# Connections_Ports.net
KiCad netlist of a schematic drawn in Altium Designer
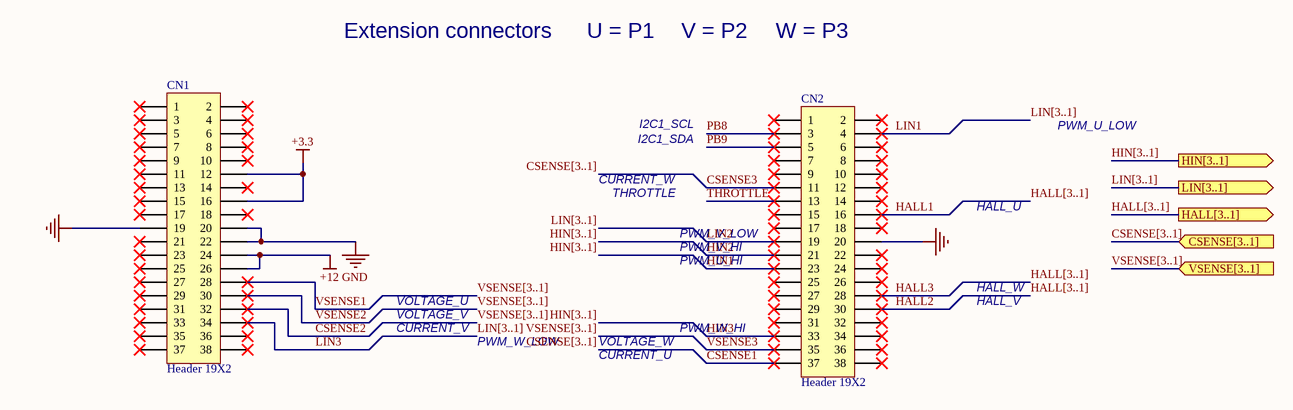
[diagram p0: Connections&Ports.SchDoc]

(export (version "E")
  (design (tool "Eeschema 10.0.6"))
  (components
    (comp (ref "CN1")
      (value "Header 19X2")
      (footprint "HDR2X19")
      (description "Header, 19-Pin, Dual row")
      (fields (field (name "PUBLISHER") "Altium Limited"))
      (libsource (lib "Nucleo_64_1") (part "Header 19X2"))
    )
    (comp (ref "CN2")
      (value "Header 19X2")
      (footprint "HDR2X19")
      (description "Header, 19-Pin, Dual row")
      (fields (field (name "PUBLISHER") "Altium Limited"))
      (libsource (lib "Nucleo_64_1") (part "Header 19X2"))
    )
  )
  (nets
    (net (code "1") (name "+3.3") (class "Default")
      (node (ref "CN1") (pin "12") (pinfunction "12_12") (pintype "passive"))
      (node (ref "CN1") (pin "16") (pinfunction "16_16") (pintype "passive"))
    )
    (net (code "2") (name "+12") (class "Default")
      (node (ref "CN1") (pin "24") (pinfunction "24_24") (pintype "passive"))
      (node (ref "CN1") (pin "26") (pinfunction "26_26") (pintype "passive"))
    )
    (net (code "3") (name "/CSENSE1") (class "Default")
      (node (ref "CN2") (pin "37") (pinfunction "37_37") (pintype "passive+no_connect"))
    )
    (net (code "4") (name "/CSENSE2") (class "Default")
      (node (ref "CN1") (pin "32") (pinfunction "32_32") (pintype "passive+no_connect"))
    )
    (net (code "5") (name "/CSENSE3") (class "Default")
      (node (ref "CN2") (pin "11") (pinfunction "11_11") (pintype "passive+no_connect"))
    )
    (net (code "7") (name "/HALL1") (class "Default")
      (node (ref "CN2") (pin "16") (pinfunction "16_16") (pintype "passive+no_connect"))
    )
    (net (code "8") (name "/HALL2") (class "Default")
      (node (ref "CN2") (pin "30") (pinfunction "30_30") (pintype "passive+no_connect"))
    )
    (net (code "9") (name "/HALL3") (class "Default")
      (node (ref "CN2") (pin "28") (pinfunction "28_28") (pintype "passive+no_connect"))
    )
    (net (code "11") (name "/HIN1") (class "Default")
      (node (ref "CN2") (pin "23") (pinfunction "23_23") (pintype "passive+no_connect"))
    )
    (net (code "12") (name "/HIN2") (class "Default")
      (node (ref "CN2") (pin "21") (pinfunction "21_21") (pintype "passive+no_connect"))
    )
    (net (code "13") (name "/HIN3") (class "Default")
      (node (ref "CN2") (pin "33") (pinfunction "33_33") (pintype "passive+no_connect"))
    )
    (net (code "15") (name "/LIN1") (class "Default")
      (node (ref "CN2") (pin "4") (pinfunction "4_4") (pintype "passive+no_connect"))
    )
    (net (code "16") (name "/LIN2") (class "Default")
      (node (ref "CN2") (pin "19") (pinfunction "19_19") (pintype "passive+no_connect"))
    )
    (net (code "17") (name "/LIN3") (class "Default")
      (node (ref "CN1") (pin "34") (pinfunction "34_34") (pintype "passive+no_connect"))
    )
    (net (code "19") (name "/PB8") (class "Default")
      (node (ref "CN2") (pin "3") (pinfunction "3_3") (pintype "passive+no_connect"))
    )
    (net (code "20") (name "/PB9") (class "Default")
      (node (ref "CN2") (pin "5") (pinfunction "5_5") (pintype "passive+no_connect"))
    )
    (net (code "21") (name "/THROTTLE") (class "Default")
      (node (ref "CN2") (pin "13") (pinfunction "13_13") (pintype "passive+no_connect"))
    )
    (net (code "22") (name "/VSENSE1") (class "Default")
      (node (ref "CN1") (pin "28") (pinfunction "28_28") (pintype "passive+no_connect"))
    )
    (net (code "23") (name "/VSENSE2") (class "Default")
      (node (ref "CN1") (pin "30") (pinfunction "30_30") (pintype "passive+no_connect"))
    )
    (net (code "24") (name "/VSENSE3") (class "Default")
      (node (ref "CN2") (pin "35") (pinfunction "35_35") (pintype "passive+no_connect"))
    )
    (net (code "26") (name "GND") (class "Default")
      (node (ref "CN1") (pin "19") (pinfunction "19_19") (pintype "passive"))
      (node (ref "CN1") (pin "20") (pinfunction "20_20") (pintype "passive"))
      (node (ref "CN1") (pin "22") (pinfunction "22_22") (pintype "passive"))
      (node (ref "CN2") (pin "20") (pinfunction "20_20") (pintype "passive"))
    )
    (net (code "27") (name "unconnected-(CN1-Pad1)") (class "Default")
      (node (ref "CN1") (pin "1") (pinfunction "1_1") (pintype "passive+no_connect"))
    )
    (net (code "28") (name "unconnected-(CN1-Pad2)") (class "Default")
      (node (ref "CN1") (pin "2") (pinfunction "2_2") (pintype "passive+no_connect"))
    )
    (net (code "29") (name "unconnected-(CN1-Pad3)") (class "Default")
      (node (ref "CN1") (pin "3") (pinfunction "3_3") (pintype "passive+no_connect"))
    )
    (net (code "30") (name "unconnected-(CN1-Pad4)") (class "Default")
      (node (ref "CN1") (pin "4") (pinfunction "4_4") (pintype "passive+no_connect"))
    )
    (net (code "31") (name "unconnected-(CN1-Pad5)") (class "Default")
      (node (ref "CN1") (pin "5") (pinfunction "5_5") (pintype "passive+no_connect"))
    )
    (net (code "32") (name "unconnected-(CN1-Pad6)") (class "Default")
      (node (ref "CN1") (pin "6") (pinfunction "6_6") (pintype "passive+no_connect"))
    )
    (net (code "33") (name "unconnected-(CN1-Pad7)") (class "Default")
      (node (ref "CN1") (pin "7") (pinfunction "7_7") (pintype "passive+no_connect"))
    )
    (net (code "34") (name "unconnected-(CN1-Pad8)") (class "Default")
      (node (ref "CN1") (pin "8") (pinfunction "8_8") (pintype "passive+no_connect"))
    )
    (net (code "35") (name "unconnected-(CN1-Pad9)") (class "Default")
      (node (ref "CN1") (pin "9") (pinfunction "9_9") (pintype "passive+no_connect"))
    )
    (net (code "36") (name "unconnected-(CN1-Pad10)") (class "Default")
      (node (ref "CN1") (pin "10") (pinfunction "10_10") (pintype "passive+no_connect"))
    )
    (net (code "37") (name "unconnected-(CN1-Pad11)") (class "Default")
      (node (ref "CN1") (pin "11") (pinfunction "11_11") (pintype "passive+no_connect"))
    )
    (net (code "38") (name "unconnected-(CN1-Pad13)") (class "Default")
      (node (ref "CN1") (pin "13") (pinfunction "13_13") (pintype "passive+no_connect"))
    )
    (net (code "39") (name "unconnected-(CN1-Pad14)") (class "Default")
      (node (ref "CN1") (pin "14") (pinfunction "14_14") (pintype "passive+no_connect"))
    )
    (net (code "40") (name "unconnected-(CN1-Pad15)") (class "Default")
      (node (ref "CN1") (pin "15") (pinfunction "15_15") (pintype "passive+no_connect"))
    )
    (net (code "41") (name "unconnected-(CN1-Pad17)") (class "Default")
      (node (ref "CN1") (pin "17") (pinfunction "17_17") (pintype "passive+no_connect"))
    )
    (net (code "42") (name "unconnected-(CN1-Pad18)") (class "Default")
      (node (ref "CN1") (pin "18") (pinfunction "18_18") (pintype "passive+no_connect"))
    )
    (net (code "43") (name "unconnected-(CN1-Pad21)") (class "Default")
      (node (ref "CN1") (pin "21") (pinfunction "21_21") (pintype "passive+no_connect"))
    )
    (net (code "44") (name "unconnected-(CN1-Pad23)") (class "Default")
      (node (ref "CN1") (pin "23") (pinfunction "23_23") (pintype "passive+no_connect"))
    )
    (net (code "45") (name "unconnected-(CN1-Pad25)") (class "Default")
      (node (ref "CN1") (pin "25") (pinfunction "25_25") (pintype "passive+no_connect"))
    )
    (net (code "46") (name "unconnected-(CN1-Pad27)") (class "Default")
      (node (ref "CN1") (pin "27") (pinfunction "27_27") (pintype "passive+no_connect"))
    )
    (net (code "47") (name "unconnected-(CN1-Pad29)") (class "Default")
      (node (ref "CN1") (pin "29") (pinfunction "29_29") (pintype "passive+no_connect"))
    )
    (net (code "48") (name "unconnected-(CN1-Pad31)") (class "Default")
      (node (ref "CN1") (pin "31") (pinfunction "31_31") (pintype "passive+no_connect"))
    )
    (net (code "49") (name "unconnected-(CN1-Pad33)") (class "Default")
      (node (ref "CN1") (pin "33") (pinfunction "33_33") (pintype "passive+no_connect"))
    )
    (net (code "50") (name "unconnected-(CN1-Pad35)") (class "Default")
      (node (ref "CN1") (pin "35") (pinfunction "35_35") (pintype "passive+no_connect"))
    )
    (net (code "51") (name "unconnected-(CN1-Pad36)") (class "Default")
      (node (ref "CN1") (pin "36") (pinfunction "36_36") (pintype "passive+no_connect"))
    )
    (net (code "52") (name "unconnected-(CN1-Pad37)") (class "Default")
      (node (ref "CN1") (pin "37") (pinfunction "37_37") (pintype "passive+no_connect"))
    )
    (net (code "53") (name "unconnected-(CN1-Pad38)") (class "Default")
      (node (ref "CN1") (pin "38") (pinfunction "38_38") (pintype "passive+no_connect"))
    )
    (net (code "54") (name "unconnected-(CN2-Pad1)") (class "Default")
      (node (ref "CN2") (pin "1") (pinfunction "1_1") (pintype "passive+no_connect"))
    )
    (net (code "55") (name "unconnected-(CN2-Pad2)") (class "Default")
      (node (ref "CN2") (pin "2") (pinfunction "2_2") (pintype "passive+no_connect"))
    )
    (net (code "56") (name "unconnected-(CN2-Pad6)") (class "Default")
      (node (ref "CN2") (pin "6") (pinfunction "6_6") (pintype "passive+no_connect"))
    )
    (net (code "57") (name "unconnected-(CN2-Pad7)") (class "Default")
      (node (ref "CN2") (pin "7") (pinfunction "7_7") (pintype "passive+no_connect"))
    )
    (net (code "58") (name "unconnected-(CN2-Pad8)") (class "Default")
      (node (ref "CN2") (pin "8") (pinfunction "8_8") (pintype "passive+no_connect"))
    )
    (net (code "59") (name "unconnected-(CN2-Pad9)") (class "Default")
      (node (ref "CN2") (pin "9") (pinfunction "9_9") (pintype "passive+no_connect"))
    )
    (net (code "60") (name "unconnected-(CN2-Pad10)") (class "Default")
      (node (ref "CN2") (pin "10") (pinfunction "10_10") (pintype "passive+no_connect"))
    )
    (net (code "61") (name "unconnected-(CN2-Pad12)") (class "Default")
      (node (ref "CN2") (pin "12") (pinfunction "12_12") (pintype "passive+no_connect"))
    )
    (net (code "62") (name "unconnected-(CN2-Pad14)") (class "Default")
      (node (ref "CN2") (pin "14") (pinfunction "14_14") (pintype "passive+no_connect"))
    )
    (net (code "63") (name "unconnected-(CN2-Pad15)") (class "Default")
      (node (ref "CN2") (pin "15") (pinfunction "15_15") (pintype "passive+no_connect"))
    )
    (net (code "64") (name "unconnected-(CN2-Pad17)") (class "Default")
      (node (ref "CN2") (pin "17") (pinfunction "17_17") (pintype "passive+no_connect"))
    )
    (net (code "65") (name "unconnected-(CN2-Pad18)") (class "Default")
      (node (ref "CN2") (pin "18") (pinfunction "18_18") (pintype "passive+no_connect"))
    )
    (net (code "66") (name "unconnected-(CN2-Pad22)") (class "Default")
      (node (ref "CN2") (pin "22") (pinfunction "22_22") (pintype "passive+no_connect"))
    )
    (net (code "67") (name "unconnected-(CN2-Pad24)") (class "Default")
      (node (ref "CN2") (pin "24") (pinfunction "24_24") (pintype "passive+no_connect"))
    )
    (net (code "68") (name "unconnected-(CN2-Pad25)") (class "Default")
      (node (ref "CN2") (pin "25") (pinfunction "25_25") (pintype "passive+no_connect"))
    )
    (net (code "69") (name "unconnected-(CN2-Pad26)") (class "Default")
      (node (ref "CN2") (pin "26") (pinfunction "26_26") (pintype "passive+no_connect"))
    )
    (net (code "70") (name "unconnected-(CN2-Pad27)") (class "Default")
      (node (ref "CN2") (pin "27") (pinfunction "27_27") (pintype "passive+no_connect"))
    )
    (net (code "71") (name "unconnected-(CN2-Pad29)") (class "Default")
      (node (ref "CN2") (pin "29") (pinfunction "29_29") (pintype "passive+no_connect"))
    )
    (net (code "72") (name "unconnected-(CN2-Pad31)") (class "Default")
      (node (ref "CN2") (pin "31") (pinfunction "31_31") (pintype "passive+no_connect"))
    )
    (net (code "73") (name "unconnected-(CN2-Pad32)") (class "Default")
      (node (ref "CN2") (pin "32") (pinfunction "32_32") (pintype "passive+no_connect"))
    )
    (net (code "74") (name "unconnected-(CN2-Pad34)") (class "Default")
      (node (ref "CN2") (pin "34") (pinfunction "34_34") (pintype "passive+no_connect"))
    )
    (net (code "75") (name "unconnected-(CN2-Pad36)") (class "Default")
      (node (ref "CN2") (pin "36") (pinfunction "36_36") (pintype "passive+no_connect"))
    )
    (net (code "76") (name "unconnected-(CN2-Pad38)") (class "Default")
      (node (ref "CN2") (pin "38") (pinfunction "38_38") (pintype "passive+no_connect"))
    )
  )
)
